# LS400.net
KiCad netlist of a schematic drawn in EAGLE
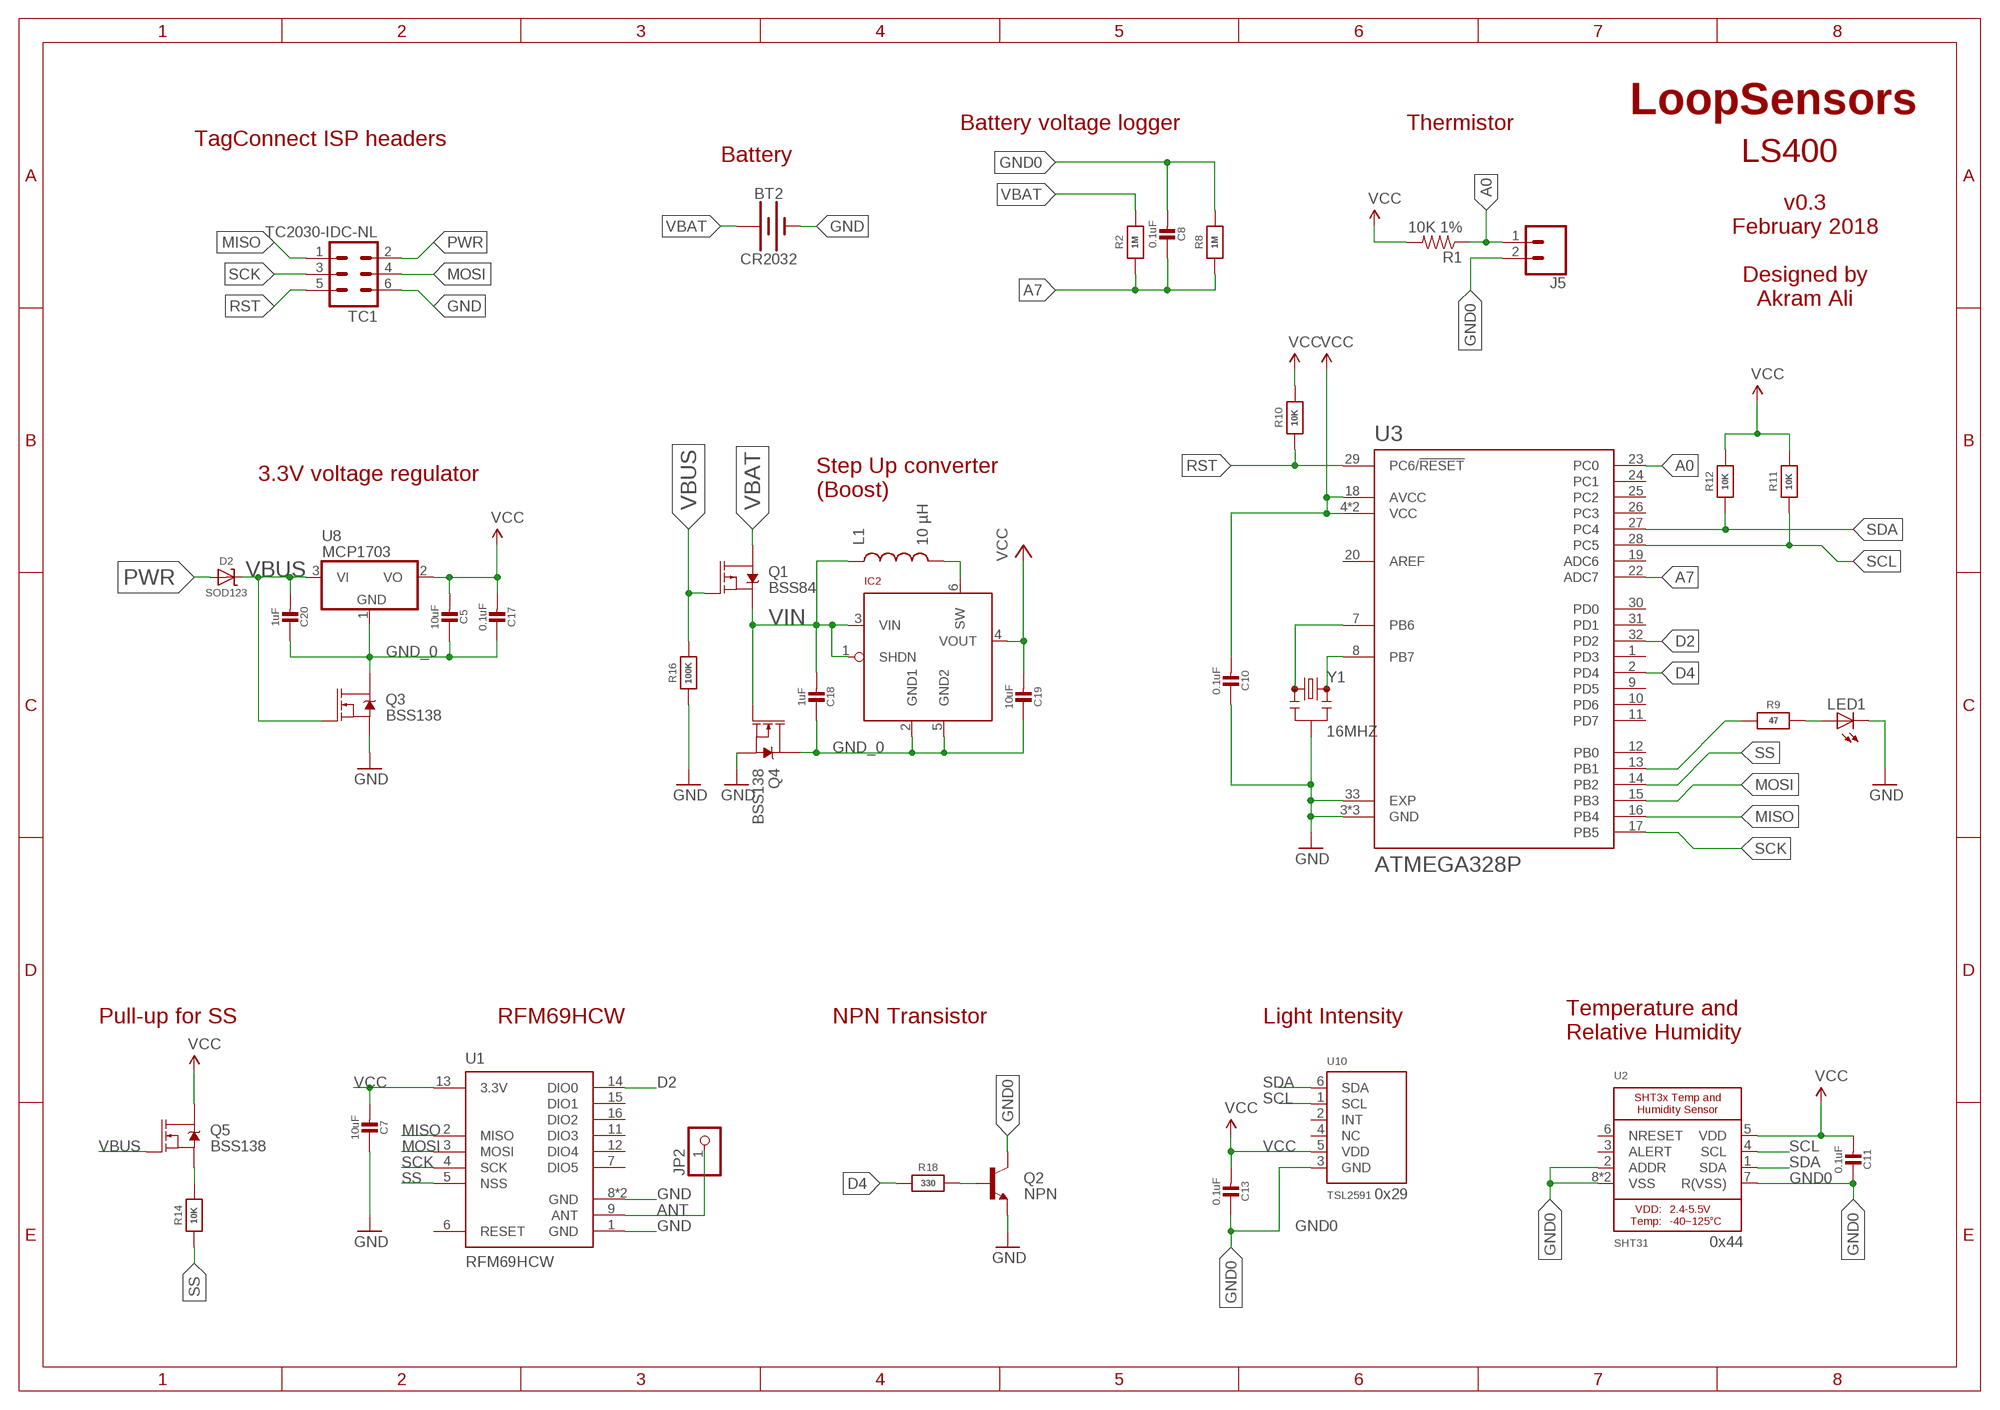
[diagram p0: schematic, sheet 1]

(export (version "E")
  (design (tool "Eeschema 10.0.6"))
  (components
    (comp (ref "BT2")
      (value "CR2032")
      (footprint "eagle-import:BATTCON_20MM_4LEGS")
      (libsource (lib "eagle-import") (part "BATTERY-20MM_SMD_4LEGS"))
    )
    (comp (ref "C5")
      (value "10uF")
      (footprint "eagle-import:MICROBUILDER__0402MP")
      (fields (field (name "MPN") "GRJ155R60J106ME11D"))
      (libsource (lib "eagle-import") (part "MICROBUILDER_CAP_CERAMIC_0402MP"))
    )
    (comp (ref "C7")
      (value "10uF")
      (footprint "eagle-import:MICROBUILDER__0402MP")
      (fields (field (name "MPN") "GRJ155R60J106ME11D"))
      (libsource (lib "eagle-import") (part "MICROBUILDER_CAP_CERAMIC_0402MP"))
    )
    (comp (ref "C8")
      (value "0.1uF")
      (footprint "eagle-import:MICROBUILDER__0402MP")
      (fields (field (name "MPN") "GRM155R71C104KA88J"))
      (libsource (lib "eagle-import") (part "MICROBUILDER_CAP_CERAMIC_0402MP"))
    )
    (comp (ref "C10")
      (value "0.1uF")
      (footprint "eagle-import:MICROBUILDER__0402MP")
      (fields (field (name "MPN") "GRJ155R60J106ME11D"))
      (libsource (lib "eagle-import") (part "MICROBUILDER_CAP_CERAMIC_0402MP"))
    )
    (comp (ref "C11")
      (value "0.1uF")
      (footprint "eagle-import:MICROBUILDER__0402MP")
      (fields (field (name "MPN") "GRJ155R60J106ME11D"))
      (libsource (lib "eagle-import") (part "MICROBUILDER_CAP_CERAMIC_0402MP"))
    )
    (comp (ref "C13")
      (value "0.1uF")
      (footprint "eagle-import:MICROBUILDER__0402MP")
      (fields (field (name "MPN") "GRJ155R60J106ME11D"))
      (libsource (lib "eagle-import") (part "MICROBUILDER_CAP_CERAMIC_0402MP"))
    )
    (comp (ref "C17")
      (value "0.1uF")
      (footprint "eagle-import:MICROBUILDER__0402MP")
      (fields (field (name "MPN") "GRJ155R60J106ME11D"))
      (libsource (lib "eagle-import") (part "MICROBUILDER_CAP_CERAMIC_0402MP"))
    )
    (comp (ref "C18")
      (value "1uF")
      (footprint "eagle-import:MICROBUILDER__0402MP")
      (fields (field (name "MPN") "GRJ155R60J106ME11D"))
      (libsource (lib "eagle-import") (part "MICROBUILDER_CAP_CERAMIC_0402MP"))
    )
    (comp (ref "C19")
      (value "10uF")
      (footprint "eagle-import:MICROBUILDER__0402MP")
      (fields (field (name "MPN") "GRJ155R60J106ME11D"))
      (libsource (lib "eagle-import") (part "MICROBUILDER_CAP_CERAMIC_0402MP"))
    )
    (comp (ref "C20")
      (value "1uF")
      (footprint "eagle-import:MICROBUILDER__0402MP")
      (fields (field (name "MPN") "GRJ155R60J106ME11D"))
      (libsource (lib "eagle-import") (part "MICROBUILDER_CAP_CERAMIC_0402MP"))
    )
    (comp (ref "D2")
      (value "SOD123")
      (footprint "eagle-import:MICROBUILDER_SOD-123")
      (fields (field (name "MPN") "SD103AW-13-F"))
      (libsource (lib "eagle-import") (part "MICROBUILDER_DIODE-SCHOTTKYSOD-123"))
    )
    (comp (ref "IC2")
      (value "LTC3525")
      (footprint "eagle-import:SC70")
      (libsource (lib "eagle-import") (part "LTC3525"))
    )
    (comp (ref "J5")
      (value "CONN_02")
      (footprint "eagle-import:1X02")
      (libsource (lib "eagle-import") (part "CONN_02"))
    )
    (comp (ref "JP2")
      (value "PINHD-1X1CB")
      (footprint "eagle-import:1X01-CLEANBIG")
      (libsource (lib "eagle-import") (part "PINHD-1X1CB"))
    )
    (comp (ref "L1")
      (value "10 µH")
      (footprint "eagle-import:1210")
      (libsource (lib "eagle-import") (part "INDUCTOR1210"))
    )
    (comp (ref "LED1")
      (value "LEDCHIPLED_0603")
      (footprint "eagle-import:CHIPLED_0603")
      (libsource (lib "eagle-import") (part "LEDCHIPLED_0603"))
    )
    (comp (ref "Q1")
      (value "BSS84")
      (footprint "eagle-import:SOT23-3")
      (libsource (lib "eagle-import") (part "MOSFET_PCH-DMG2307L"))
    )
    (comp (ref "Q2")
      (value "NPN")
      (footprint "eagle-import:SOT23-3")
      (libsource (lib "eagle-import") (part "TRANSISTOR_NPNMMBT5088"))
    )
    (comp (ref "Q3")
      (value "BSS138")
      (footprint "eagle-import:SOT23-3")
      (libsource (lib "eagle-import") (part "MOSFET-NCH-BSS138"))
    )
    (comp (ref "Q4")
      (value "BSS138")
      (footprint "eagle-import:SOT23-3")
      (libsource (lib "eagle-import") (part "MOSFET-NCH-BSS138"))
    )
    (comp (ref "Q5")
      (value "BSS138")
      (footprint "eagle-import:SOT23-3")
      (libsource (lib "eagle-import") (part "MOSFET-NCH-BSS138"))
    )
    (comp (ref "R1")
      (value "10K 1%")
      (footprint "eagle-import:0805")
      (libsource (lib "eagle-import") (part "RESISTOR0805-RES"))
    )
    (comp (ref "R2")
      (value "1M")
      (footprint "eagle-import:MICROBUILDER__0402MP")
      (fields (field (name "MPN") "RC0402JR-0710KL"))
      (libsource (lib "eagle-import") (part "MICROBUILDER_RESISTOR_0402MP"))
    )
    (comp (ref "R8")
      (value "1M")
      (footprint "eagle-import:MICROBUILDER__0402MP")
      (fields (field (name "MPN") "RC0402JR-0710KL"))
      (libsource (lib "eagle-import") (part "MICROBUILDER_RESISTOR_0402MP"))
    )
    (comp (ref "R9")
      (value "47")
      (footprint "eagle-import:MICROBUILDER__0402MP")
      (fields (field (name "MPN") "RC0402JR-071KL"))
      (libsource (lib "eagle-import") (part "Adafruit PowerBoost 1000C Rev B_MICROBUILDER_RESISTOR_0402MP"))
    )
    (comp (ref "R10")
      (value "10K")
      (footprint "eagle-import:MICROBUILDER__0402MP")
      (fields (field (name "MPN") "RC0402JR-071KL"))
      (libsource (lib "eagle-import") (part "Adafruit PowerBoost 1000C Rev B_MICROBUILDER_RESISTOR_0402MP"))
    )
    (comp (ref "R11")
      (value "10K")
      (footprint "eagle-import:MICROBUILDER__0402MP")
      (fields (field (name "MPN") "RC0402JR-071KL"))
      (libsource (lib "eagle-import") (part "Adafruit PowerBoost 1000C Rev B_MICROBUILDER_RESISTOR_0402MP"))
    )
    (comp (ref "R12")
      (value "10K")
      (footprint "eagle-import:MICROBUILDER__0402MP")
      (fields (field (name "MPN") "RC0402JR-071KL"))
      (libsource (lib "eagle-import") (part "Adafruit PowerBoost 1000C Rev B_MICROBUILDER_RESISTOR_0402MP"))
    )
    (comp (ref "R14")
      (value "10K")
      (footprint "eagle-import:MICROBUILDER__0402MP")
      (fields (field (name "MPN") "RC0402JR-071KL"))
      (libsource (lib "eagle-import") (part "Adafruit PowerBoost 1000C Rev B_MICROBUILDER_RESISTOR_0402MP"))
    )
    (comp (ref "R16")
      (value "100K")
      (footprint "eagle-import:MICROBUILDER__0402MP")
      (fields (field (name "MPN") "RC0402JR-071KL"))
      (libsource (lib "eagle-import") (part "Adafruit PowerBoost 1000C Rev B_MICROBUILDER_RESISTOR_0402MP"))
    )
    (comp (ref "R18")
      (value "330")
      (footprint "eagle-import:MICROBUILDER__0402MP")
      (fields (field (name "MPN") "RC0402JR-071KL"))
      (libsource (lib "eagle-import") (part "Adafruit PowerBoost 1000C Rev B_MICROBUILDER_RESISTOR_0402MP"))
    )
    (comp (ref "TC1")
      (value "TC2030-IDC-NL")
      (footprint "eagle-import:TC2030-IDC-NL")
      (libsource (lib "eagle-import") (part "TC2030-IDC-NL"))
    )
    (comp (ref "U1")
      (value "RFM69HCW")
      (footprint "eagle-import:RFM69HCW-XXXS2")
      (libsource (lib "eagle-import") (part "RFM69HCW"))
    )
    (comp (ref "U2")
      (value "SHT31")
      (footprint "eagle-import:SHT3X")
      (fields (field (name "MPN") "SHT35-DIS-B"))
      (libsource (lib "eagle-import") (part "SHT3X"))
    )
    (comp (ref "U3")
      (value "ATMEGA328P")
      (footprint "eagle-import:QFN50P500X500X100-33N")
      (fields (field (name "MF") "Atmel") (field (name "MP") "ATMEGA328P-MU"))
      (libsource (lib "eagle-import") (part "ATMEGA328P-MU"))
    )
    (comp (ref "U8")
      (value "MCP1703")
      (footprint "eagle-import:SOT23")
      (fields (field (name "MPN") "MCP1703T-2502E/CB"))
      (libsource (lib "eagle-import") (part "MCP1703CB"))
    )
    (comp (ref "U10")
      (value "TSL2591")
      (footprint "eagle-import:DFN6_TAOS")
      (fields (field (name "MPN") "TSL25911FN "))
      (libsource (lib "eagle-import") (part "LIGHT_TSL2591"))
    )
    (comp (ref "Y1")
      (value "16MHZ")
      (footprint "eagle-import:RESONATOR-SMD")
      (libsource (lib "eagle-import") (part "RESONATOR16MHZ"))
    )
  )
  (nets
    (net (code "1") (name "/ANT") (class "Default")
      (node (ref "JP2") (pin "1") (pinfunction "1_1") (pintype "passive"))
      (node (ref "U1") (pin "9") (pinfunction "ANT_9") (pintype "passive"))
    )
    (net (code "2") (name "/GND_0") (class "Default")
      (node (ref "C17") (pin "1") (pinfunction "1_1") (pintype "passive"))
      (node (ref "C18") (pin "1") (pinfunction "1_1") (pintype "passive"))
      (node (ref "C19") (pin "1") (pinfunction "1_1") (pintype "passive"))
      (node (ref "C20") (pin "1") (pinfunction "1_1") (pintype "passive"))
      (node (ref "C5") (pin "1") (pinfunction "1_1") (pintype "passive"))
      (node (ref "IC2") (pin "2") (pinfunction "GND1_2") (pintype "power_in"))
      (node (ref "IC2") (pin "5") (pinfunction "GND2_5") (pintype "power_in"))
      (node (ref "Q3") (pin "3") (pinfunction "D_3") (pintype "bidirectional"))
      (node (ref "Q4") (pin "3") (pinfunction "D_3") (pintype "bidirectional"))
      (node (ref "U8") (pin "1") (pinfunction "GND_1") (pintype "passive"))
    )
    (net (code "3") (name "/VIN") (class "Default")
      (node (ref "C18") (pin "2") (pinfunction "2_2") (pintype "passive"))
      (node (ref "IC2") (pin "1") (pinfunction "SHDN_1") (pintype "input"))
      (node (ref "IC2") (pin "3") (pinfunction "VIN_3") (pintype "tri_state"))
      (node (ref "L1") (pin "1") (pinfunction "1_1") (pintype "passive"))
      (node (ref "Q1") (pin "2") (pinfunction "S_2") (pintype "bidirectional"))
      (node (ref "Q4") (pin "1") (pinfunction "G_1") (pintype "bidirectional"))
    )
    (net (code "4") (name "A0") (class "Default")
      (node (ref "J5") (pin "1") (pinfunction "1_1") (pintype "passive"))
      (node (ref "R1") (pin "1") (pinfunction "1_1") (pintype "passive"))
      (node (ref "U3") (pin "23") (pinfunction "PC0_23") (pintype "bidirectional"))
    )
    (net (code "5") (name "A7") (class "Default")
      (node (ref "C8") (pin "1") (pinfunction "1_1") (pintype "passive"))
      (node (ref "R2") (pin "1") (pinfunction "1_1") (pintype "passive"))
      (node (ref "R8") (pin "1") (pinfunction "1_1") (pintype "passive"))
      (node (ref "U3") (pin "22") (pinfunction "ADC7_22") (pintype "bidirectional"))
    )
    (net (code "6") (name "D2") (class "Default")
      (node (ref "U1") (pin "14") (pinfunction "DIO0_14") (pintype "bidirectional"))
      (node (ref "U3") (pin "32") (pinfunction "PD2_32") (pintype "bidirectional"))
    )
    (net (code "7") (name "D4") (class "Default")
      (node (ref "R18") (pin "1") (pinfunction "1_1") (pintype "passive"))
      (node (ref "U3") (pin "2") (pinfunction "PD4_2") (pintype "bidirectional"))
    )
    (net (code "8") (name "GND") (class "Default")
      (node (ref "BT2") (pin "NEGATIVE") (pinfunction "-_NEGATIVE") (pintype "power_in"))
      (node (ref "C10") (pin "1") (pinfunction "1_1") (pintype "passive"))
      (node (ref "C7") (pin "1") (pinfunction "1_1") (pintype "passive"))
      (node (ref "LED1") (pin "C") (pinfunction "C_C") (pintype "passive"))
      (node (ref "Q2") (pin "2") (pinfunction "E_2") (pintype "passive"))
      (node (ref "Q3") (pin "2") (pinfunction "S_2") (pintype "bidirectional"))
      (node (ref "Q4") (pin "2") (pinfunction "S_2") (pintype "bidirectional"))
      (node (ref "R16") (pin "1") (pinfunction "1_1") (pintype "passive"))
      (node (ref "TC1") (pin "6") (pinfunction "6_6") (pintype "passive"))
      (node (ref "U1") (pin "1") (pinfunction "GND_1") (pintype "power_in"))
      (node (ref "U1") (pin "10") (pinfunction "GND_10") (pintype "power_in"))
      (node (ref "U1") (pin "8") (pinfunction "GND_8") (pintype "power_in"))
      (node (ref "U3") (pin "21") (pinfunction "GND_21") (pintype "power_in"))
      (node (ref "U3") (pin "3") (pinfunction "GND_3") (pintype "power_in"))
      (node (ref "U3") (pin "33") (pinfunction "EXP_33") (pintype "power_in"))
      (node (ref "U3") (pin "5") (pinfunction "GND_5") (pintype "power_in"))
      (node (ref "Y1") (pin "2") (pinfunction "2_2") (pintype "passive"))
    )
    (net (code "9") (name "GND0") (class "Default")
      (node (ref "C11") (pin "1") (pinfunction "1_1") (pintype "passive"))
      (node (ref "C13") (pin "1") (pinfunction "1_1") (pintype "passive"))
      (node (ref "C8") (pin "2") (pinfunction "2_2") (pintype "passive"))
      (node (ref "J5") (pin "2") (pinfunction "2_2") (pintype "passive"))
      (node (ref "Q2") (pin "3") (pinfunction "C_3") (pintype "passive"))
      (node (ref "R8") (pin "2") (pinfunction "2_2") (pintype "passive"))
      (node (ref "U10") (pin "3") (pinfunction "GND_3") (pintype "power_in"))
      (node (ref "U2") (pin "2") (pinfunction "ADDR_2") (pintype "bidirectional"))
      (node (ref "U2") (pin "7") (pinfunction "R(VSS)_7") (pintype "bidirectional"))
      (node (ref "U2") (pin "8") (pinfunction "VSS_8") (pintype "power_in"))
      (node (ref "U2") (pin "THERMAL") (pinfunction "VSS_THERMAL") (pintype "power_in"))
    )
    (net (code "10") (name "MISO") (class "Default")
      (node (ref "TC1") (pin "1") (pinfunction "1_1") (pintype "passive"))
      (node (ref "U1") (pin "2") (pinfunction "MISO_2") (pintype "bidirectional"))
      (node (ref "U3") (pin "16") (pinfunction "PB4_16") (pintype "bidirectional"))
    )
    (net (code "11") (name "MOSI") (class "Default")
      (node (ref "TC1") (pin "4") (pinfunction "4_4") (pintype "passive"))
      (node (ref "U1") (pin "3") (pinfunction "MOSI_3") (pintype "input"))
      (node (ref "U3") (pin "15") (pinfunction "PB3_15") (pintype "bidirectional"))
    )
    (net (code "12") (name "Net-(IC2-SW)") (class "Default")
      (node (ref "IC2") (pin "6") (pinfunction "SW_6") (pintype "power_in"))
      (node (ref "L1") (pin "2") (pinfunction "2_2") (pintype "passive"))
    )
    (net (code "13") (name "Net-(LED1-PadA)") (class "Default")
      (node (ref "LED1") (pin "A") (pinfunction "A_A") (pintype "passive"))
      (node (ref "R9") (pin "2") (pinfunction "2_2") (pintype "passive"))
    )
    (net (code "14") (name "Net-(Q2-B)") (class "Default")
      (node (ref "Q2") (pin "1") (pinfunction "B_1") (pintype "passive"))
      (node (ref "R18") (pin "2") (pinfunction "2_2") (pintype "passive"))
    )
    (net (code "15") (name "Net-(Q5-S)") (class "Default")
      (node (ref "Q5") (pin "2") (pinfunction "S_2") (pintype "bidirectional"))
      (node (ref "R14") (pin "2") (pinfunction "2_2") (pintype "passive"))
    )
    (net (code "16") (name "Net-(U3-PB1)") (class "Default")
      (node (ref "R9") (pin "1") (pinfunction "1_1") (pintype "passive"))
      (node (ref "U3") (pin "13") (pinfunction "PB1_13") (pintype "bidirectional"))
    )
    (net (code "17") (name "Net-(U3-PB6)") (class "Default")
      (node (ref "U3") (pin "7") (pinfunction "PB6_7") (pintype "bidirectional"))
      (node (ref "Y1") (pin "1") (pinfunction "1_1") (pintype "passive"))
    )
    (net (code "18") (name "Net-(U3-PB7)") (class "Default")
      (node (ref "U3") (pin "8") (pinfunction "PB7_8") (pintype "bidirectional"))
      (node (ref "Y1") (pin "3") (pinfunction "3_3") (pintype "passive"))
    )
    (net (code "19") (name "PWR") (class "Default")
      (node (ref "D2") (pin "A") (pinfunction "A_A") (pintype "passive"))
      (node (ref "TC1") (pin "2") (pinfunction "2_2") (pintype "passive"))
    )
    (net (code "20") (name "RST") (class "Default")
      (node (ref "R10") (pin "1") (pinfunction "1_1") (pintype "passive"))
      (node (ref "TC1") (pin "5") (pinfunction "5_5") (pintype "passive"))
      (node (ref "U3") (pin "29") (pinfunction "PC6/~{RESET}_29") (pintype "bidirectional"))
    )
    (net (code "21") (name "SCK") (class "Default")
      (node (ref "TC1") (pin "3") (pinfunction "3_3") (pintype "passive"))
      (node (ref "U1") (pin "4") (pinfunction "SCK_4") (pintype "input"))
      (node (ref "U3") (pin "17") (pinfunction "PB5_17") (pintype "bidirectional"))
    )
    (net (code "22") (name "SCL") (class "Default")
      (node (ref "R11") (pin "1") (pinfunction "1_1") (pintype "passive"))
      (node (ref "U10") (pin "1") (pinfunction "SCL_1") (pintype "bidirectional"))
      (node (ref "U2") (pin "4") (pinfunction "SCL_4") (pintype "bidirectional"))
      (node (ref "U3") (pin "28") (pinfunction "PC5_28") (pintype "bidirectional"))
    )
    (net (code "23") (name "SDA") (class "Default")
      (node (ref "R12") (pin "1") (pinfunction "1_1") (pintype "passive"))
      (node (ref "U10") (pin "6") (pinfunction "SDA_6") (pintype "bidirectional"))
      (node (ref "U2") (pin "1") (pinfunction "SDA_1") (pintype "bidirectional"))
      (node (ref "U3") (pin "27") (pinfunction "PC4_27") (pintype "bidirectional"))
    )
    (net (code "24") (name "SS") (class "Default")
      (node (ref "R14") (pin "1") (pinfunction "1_1") (pintype "passive"))
      (node (ref "U1") (pin "5") (pinfunction "NSS_5") (pintype "input"))
      (node (ref "U3") (pin "14") (pinfunction "PB2_14") (pintype "bidirectional"))
    )
    (net (code "25") (name "VBAT") (class "Default")
      (node (ref "BT2") (pin "POSITIVE@1") (pinfunction "+_POSITIVE@1") (pintype "power_in"))
      (node (ref "BT2") (pin "POSITIVE@2") (pinfunction "+_POSITIVE@2") (pintype "power_in"))
      (node (ref "BT2") (pin "POSITIVE@3") (pinfunction "+_POSITIVE@3") (pintype "power_in"))
      (node (ref "BT2") (pin "POSITIVE@4") (pinfunction "+_POSITIVE@4") (pintype "power_in"))
      (node (ref "Q1") (pin "3") (pinfunction "D_3") (pintype "bidirectional"))
      (node (ref "R2") (pin "2") (pinfunction "2_2") (pintype "passive"))
    )
    (net (code "26") (name "VBUS") (class "Default")
      (node (ref "C20") (pin "2") (pinfunction "2_2") (pintype "passive"))
      (node (ref "D2") (pin "C") (pinfunction "C_C") (pintype "passive"))
      (node (ref "Q1") (pin "1") (pinfunction "G_1") (pintype "bidirectional"))
      (node (ref "Q3") (pin "1") (pinfunction "G_1") (pintype "bidirectional"))
      (node (ref "Q5") (pin "1") (pinfunction "G_1") (pintype "bidirectional"))
      (node (ref "R16") (pin "2") (pinfunction "2_2") (pintype "passive"))
      (node (ref "U8") (pin "3") (pinfunction "VI_3") (pintype "input"))
    )
    (net (code "27") (name "VCC") (class "Default")
      (node (ref "C10") (pin "2") (pinfunction "2_2") (pintype "passive"))
      (node (ref "C11") (pin "2") (pinfunction "2_2") (pintype "passive"))
      (node (ref "C13") (pin "2") (pinfunction "2_2") (pintype "passive"))
      (node (ref "C17") (pin "2") (pinfunction "2_2") (pintype "passive"))
      (node (ref "C19") (pin "2") (pinfunction "2_2") (pintype "passive"))
      (node (ref "C5") (pin "2") (pinfunction "2_2") (pintype "passive"))
      (node (ref "C7") (pin "2") (pinfunction "2_2") (pintype "passive"))
      (node (ref "IC2") (pin "4") (pinfunction "VOUT_4") (pintype "power_in"))
      (node (ref "Q5") (pin "3") (pinfunction "D_3") (pintype "bidirectional"))
      (node (ref "R1") (pin "2") (pinfunction "2_2") (pintype "passive"))
      (node (ref "R10") (pin "2") (pinfunction "2_2") (pintype "passive"))
      (node (ref "R11") (pin "2") (pinfunction "2_2") (pintype "passive"))
      (node (ref "R12") (pin "2") (pinfunction "2_2") (pintype "passive"))
      (node (ref "U1") (pin "13") (pinfunction "3.3V_13") (pintype "power_in"))
      (node (ref "U10") (pin "5") (pinfunction "VDD_5") (pintype "power_in"))
      (node (ref "U2") (pin "5") (pinfunction "VDD_5") (pintype "power_in"))
      (node (ref "U3") (pin "18") (pinfunction "AVCC_18") (pintype "power_in"))
      (node (ref "U3") (pin "4") (pinfunction "VCC_4") (pintype "power_in"))
      (node (ref "U3") (pin "6") (pinfunction "VCC_6") (pintype "power_in"))
      (node (ref "U8") (pin "2") (pinfunction "VO_2") (pintype "passive"))
    )
    (net (code "28") (name "unconnected-(U1-DIO1-Pad15)") (class "Default")
      (node (ref "U1") (pin "15") (pinfunction "DIO1_15") (pintype "bidirectional"))
    )
    (net (code "29") (name "unconnected-(U1-DIO2-Pad16)") (class "Default")
      (node (ref "U1") (pin "16") (pinfunction "DIO2_16") (pintype "bidirectional"))
    )
    (net (code "30") (name "unconnected-(U1-DIO3-Pad11)") (class "Default")
      (node (ref "U1") (pin "11") (pinfunction "DIO3_11") (pintype "bidirectional"))
    )
    (net (code "31") (name "unconnected-(U1-DIO4-Pad12)") (class "Default")
      (node (ref "U1") (pin "12") (pinfunction "DIO4_12") (pintype "bidirectional"))
    )
    (net (code "32") (name "unconnected-(U1-DIO5-Pad7)") (class "Default")
      (node (ref "U1") (pin "7") (pinfunction "DIO5_7") (pintype "bidirectional"))
    )
    (net (code "33") (name "unconnected-(U1-RESET-Pad6)") (class "Default")
      (node (ref "U1") (pin "6") (pinfunction "RESET_6") (pintype "input"))
    )
    (net (code "34") (name "unconnected-(U2-ALERT-Pad3)") (class "Default")
      (node (ref "U2") (pin "3") (pinfunction "ALERT_3") (pintype "bidirectional"))
    )
    (net (code "35") (name "unconnected-(U2-NRESET-Pad6)") (class "Default")
      (node (ref "U2") (pin "6") (pinfunction "NRESET_6") (pintype "bidirectional"))
    )
    (net (code "36") (name "unconnected-(U3-ADC6-Pad19)") (class "Default")
      (node (ref "U3") (pin "19") (pinfunction "ADC6_19") (pintype "bidirectional"))
    )
    (net (code "37") (name "unconnected-(U3-AREF-Pad20)") (class "Default")
      (node (ref "U3") (pin "20") (pinfunction "AREF_20") (pintype "input"))
    )
    (net (code "38") (name "unconnected-(U3-PB0-Pad12)") (class "Default")
      (node (ref "U3") (pin "12") (pinfunction "PB0_12") (pintype "bidirectional"))
    )
    (net (code "39") (name "unconnected-(U3-PC1-Pad24)") (class "Default")
      (node (ref "U3") (pin "24") (pinfunction "PC1_24") (pintype "bidirectional"))
    )
    (net (code "40") (name "unconnected-(U3-PC2-Pad25)") (class "Default")
      (node (ref "U3") (pin "25") (pinfunction "PC2_25") (pintype "bidirectional"))
    )
    (net (code "41") (name "unconnected-(U3-PC3-Pad26)") (class "Default")
      (node (ref "U3") (pin "26") (pinfunction "PC3_26") (pintype "bidirectional"))
    )
    (net (code "42") (name "unconnected-(U3-PD0-Pad30)") (class "Default")
      (node (ref "U3") (pin "30") (pinfunction "PD0_30") (pintype "bidirectional"))
    )
    (net (code "43") (name "unconnected-(U3-PD1-Pad31)") (class "Default")
      (node (ref "U3") (pin "31") (pinfunction "PD1_31") (pintype "bidirectional"))
    )
    (net (code "44") (name "unconnected-(U3-PD3-Pad1)") (class "Default")
      (node (ref "U3") (pin "1") (pinfunction "PD3_1") (pintype "bidirectional"))
    )
    (net (code "45") (name "unconnected-(U3-PD5-Pad9)") (class "Default")
      (node (ref "U3") (pin "9") (pinfunction "PD5_9") (pintype "bidirectional"))
    )
    (net (code "46") (name "unconnected-(U3-PD6-Pad10)") (class "Default")
      (node (ref "U3") (pin "10") (pinfunction "PD6_10") (pintype "bidirectional"))
    )
    (net (code "47") (name "unconnected-(U3-PD7-Pad11)") (class "Default")
      (node (ref "U3") (pin "11") (pinfunction "PD7_11") (pintype "bidirectional"))
    )
    (net (code "48") (name "unconnected-(U10-INT-Pad2)") (class "Default")
      (node (ref "U10") (pin "2") (pinfunction "INT_2") (pintype "output"))
    )
    (net (code "49") (name "unconnected-(U10-NC-Pad4)") (class "Default")
      (node (ref "U10") (pin "4") (pinfunction "NC_4") (pintype "no_connect"))
    )
  )
)
